# tiny10.net
KiCad netlist of a schematic drawn in EAGLE
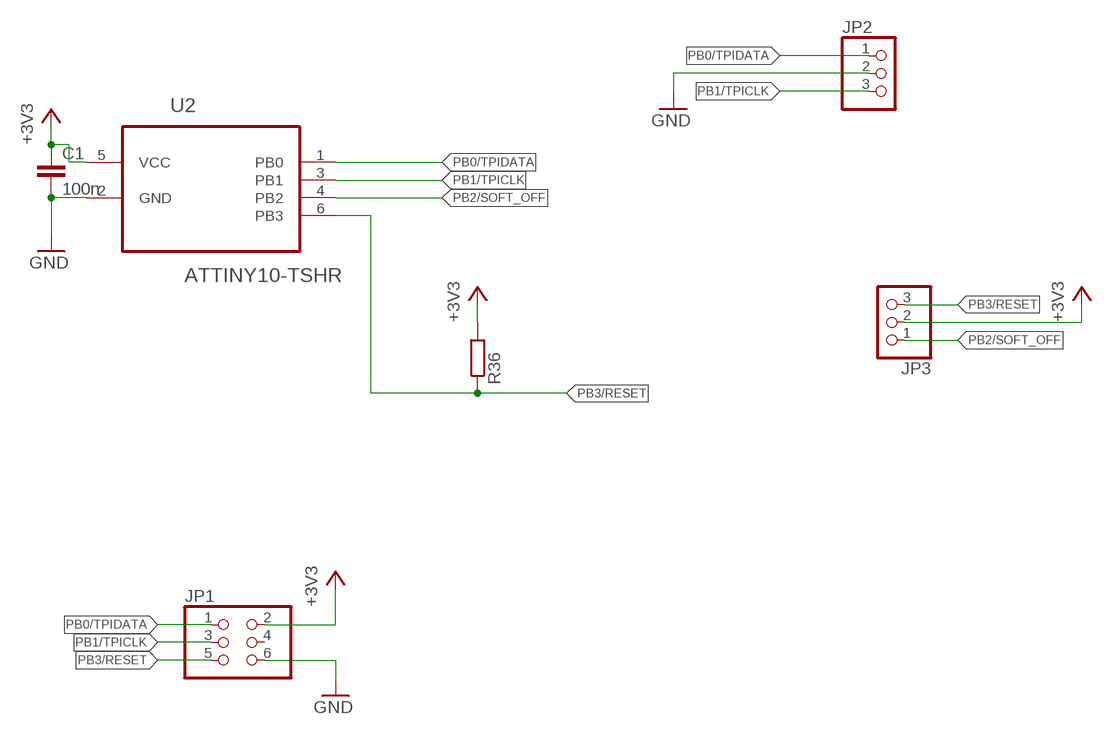
[diagram p0: schematic, sheet 1]

(export (version "E")
  (design (tool "Eeschema 10.0.6"))
  (components
    (comp (ref "C1")
      (value "100n")
      (footprint "eagle-import:C0603")
      (libsource (lib "eagle-import") (part "C-EUC0603"))
    )
    (comp (ref "JP1")
      (value "PINHD-2X3")
      (footprint "eagle-import:2X03")
      (libsource (lib "eagle-import") (part "PINHD-2X3"))
    )
    (comp (ref "JP2")
      (value "PINHD-1X3")
      (footprint "eagle-import:1X03")
      (libsource (lib "eagle-import") (part "PINHD-1X3"))
    )
    (comp (ref "JP3")
      (value "PINHD-1X3")
      (footprint "eagle-import:1X03")
      (libsource (lib "eagle-import") (part "PINHD-1X3"))
    )
    (comp (ref "R36")
      (value "R-EU_M0805")
      (footprint "eagle-import:M0805")
      (libsource (lib "eagle-import") (part "R-EU_M0805"))
    )
    (comp (ref "U2")
      (value "ATTINY10-TSHR")
      (footprint "eagle-import:SOT95P280X145-6N")
      (libsource (lib "eagle-import") (part "ATTINY10-TSHR"))
    )
  )
  (nets
    (net (code "1") (name "+3V3") (class "Default")
      (node (ref "C1") (pin "1") (pinfunction "1_1") (pintype "passive"))
      (node (ref "JP1") (pin "2") (pinfunction "2_2") (pintype "passive"))
      (node (ref "JP3") (pin "2") (pinfunction "2_2") (pintype "passive"))
      (node (ref "R36") (pin "2") (pinfunction "2_2") (pintype "passive"))
      (node (ref "U2") (pin "5") (pinfunction "VCC_5") (pintype "power_in"))
    )
    (net (code "2") (name "GND") (class "Default")
      (node (ref "C1") (pin "2") (pinfunction "2_2") (pintype "passive"))
      (node (ref "JP1") (pin "6") (pinfunction "6_6") (pintype "passive"))
      (node (ref "JP2") (pin "2") (pinfunction "2_2") (pintype "passive"))
      (node (ref "U2") (pin "2") (pinfunction "GND_2") (pintype "passive"))
    )
    (net (code "3") (name "PB0{slash}TPIDATA") (class "Default")
      (node (ref "JP1") (pin "1") (pinfunction "1_1") (pintype "passive"))
      (node (ref "JP2") (pin "1") (pinfunction "1_1") (pintype "passive"))
      (node (ref "U2") (pin "1") (pinfunction "PB0_1") (pintype "bidirectional"))
    )
    (net (code "4") (name "PB1{slash}TPICLK") (class "Default")
      (node (ref "JP1") (pin "3") (pinfunction "3_3") (pintype "passive"))
      (node (ref "JP2") (pin "3") (pinfunction "3_3") (pintype "passive"))
      (node (ref "U2") (pin "3") (pinfunction "PB1_3") (pintype "bidirectional"))
    )
    (net (code "5") (name "PB2{slash}SOFT_OFF") (class "Default")
      (node (ref "JP3") (pin "1") (pinfunction "1_1") (pintype "passive"))
      (node (ref "U2") (pin "4") (pinfunction "PB2_4") (pintype "bidirectional"))
    )
    (net (code "6") (name "PB3{slash}RESET") (class "Default")
      (node (ref "JP1") (pin "5") (pinfunction "5_5") (pintype "passive"))
      (node (ref "JP3") (pin "3") (pinfunction "3_3") (pintype "passive"))
      (node (ref "R36") (pin "1") (pinfunction "1_1") (pintype "passive"))
      (node (ref "U2") (pin "6") (pinfunction "PB3_6") (pintype "bidirectional"))
    )
    (net (code "7") (name "unconnected-(JP1-Pad4)") (class "Default")
      (node (ref "JP1") (pin "4") (pinfunction "4_4") (pintype "passive"))
    )
  )
)
